# CP2102.net
KiCad netlist of a schematic drawn in Altium Designer
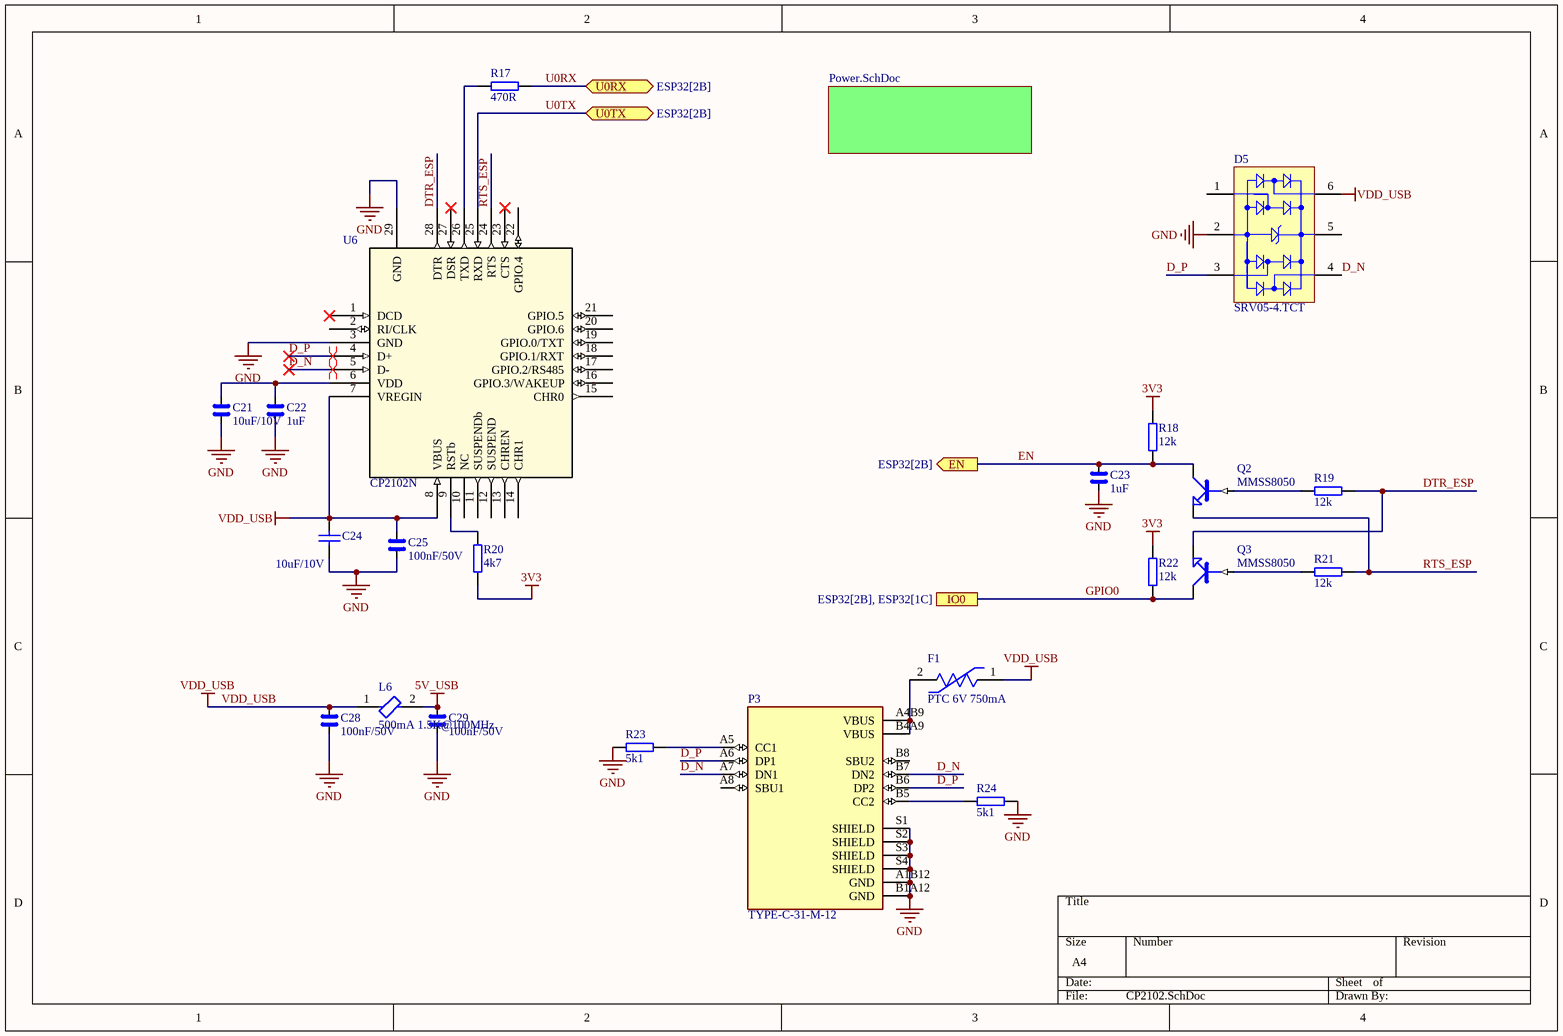
[diagram p0: CP2102.SchDoc]

(export (version "E")
  (design (tool "Eeschema 10.0.6"))
  (components
    (comp (ref "C21")
      (value "10uF/10V")
      (footprint "1608[0603]")
      (description "Capacitor")
      (fields (field (name "LCSCPARTNO") "C19702"))
      (libsource (lib "Sch") (part "C"))
    )
    (comp (ref "C22")
      (value "1uF")
      (footprint "1608[0603]")
      (description "CAP CER 1UF 10V X5R 0603")
      (fields (field (name "LCSCPARTNO") "C15849"))
      (libsource (lib "Sch") (part "C"))
    )
    (comp (ref "C23")
      (value "1uF")
      (footprint "1608[0603]")
      (description "CAP CER 1UF 10V X5R 0603")
      (fields (field (name "LCSCPARTNO") "C15849"))
      (libsource (lib "Sch") (part "C"))
    )
    (comp (ref "C24")
      (value "10uF/10V")
      (footprint "1608[0603]")
      (description "Capacitor")
      (fields (field (name "LCSCPARTNO") "C19702"))
      (libsource (lib "Sch") (part "Cap"))
    )
    (comp (ref "C25")
      (value "100nF/50V")
      (footprint "1608[0603]")
      (description "Cap Ceramic 0.1uF 50V X7R 20% SMD 0603 125C Paper T/R")
      (fields (field (name "LCSCPARTNO") "C14663"))
      (libsource (lib "Sch") (part "C"))
    )
    (comp (ref "C28")
      (value "100nF/50V")
      (footprint "1608[0603]")
      (description "Cap Ceramic 0.1uF 50V X7R 20% SMD 0603 125C Paper T/R")
      (fields (field (name "LCSCPARTNO") "C14663"))
      (libsource (lib "Sch") (part "C"))
    )
    (comp (ref "C29")
      (value "100nF/50V")
      (footprint "1608[0603]")
      (description "Cap Ceramic 0.1uF 50V X7R 20% SMD 0603 125C Paper T/R")
      (fields (field (name "LCSCPARTNO") "C14663"))
      (libsource (lib "Sch") (part "C"))
    )
    (comp (ref "D5")
      (value "SRV05-4.TCT")
      (footprint "SMTC-SOT23-6_V")
      (fields (field (name "LCSCPARTNO") "C85364"))
      (libsource (lib "Altium Content Vault") (part "STM-USB_DVI_HDMIULC6-4SC6X-SOT23-6L"))
    )
    (comp (ref "F1")
      (value "PTC 6V 750mA")
      (footprint "FP-1206L050YR-MFG")
      (description "PTC RESET FUSE 6V 750MA 1206")
      (fields (field (name "LCSCPARTNO") "C70078"))
      (libsource (lib "Altium Content Vault") (part "fdf083d5f6389a9a1c4e51137f46658"))
    )
    (comp (ref "L6")
      (value "500mA 1.5K@100MHz")
      (footprint "1608[0603]")
      (description "Chip Ferrite Bead, 0603, 1500Ω @ 100MHz, 0.5Ω, 25%, 500mA")
      (fields (field (name "LCSCPARTNO") "C82155"))
      (libsource (lib "Altium Content Vault") (part "5f30dd21d616792df468990f7003faa"))
    )
    (comp (ref "P3")
      (value "TYPE-C-31-M-12")
      (footprint "HRO_TYPE-C-31-M-12-3D")
      (description "USB Connectors 24 Receptacle 1 8.94*7.3mm RoHS")
      (fields (field (name "LCSCPARTNO") "C165948"))
      (libsource (lib "TYPE-C-31-M-12") (part "TYPE-C-31-M-12"))
    )
    (comp (ref "Q2")
      (value "MMSS8050")
      (footprint "SOT-23")
      (description "TRANS NPN 25V 1.5A SOT23")
      (fields (field (name "LCSCPARTNO") "C20526"))
      (libsource (lib "Sch") (part "NPN1"))
    )
    (comp (ref "Q3")
      (value "MMSS8050")
      (footprint "SOT-23")
      (description "TRANS NPN 25V 1.5A SOT23")
      (fields (field (name "LCSCPARTNO") "C20526"))
      (libsource (lib "Sch") (part "NPN1"))
    )
    (comp (ref "R17")
      (value "470R")
      (footprint "1608[0603]")
      (fields (field (name "LCSCPARTNO") "C23179"))
      (libsource (lib "Sch") (part "R"))
    )
    (comp (ref "R18")
      (value "12k")
      (footprint "1608[0603]")
      (description "Res Thick Film 0603 12K Ohm 1% 1/10W 100ppm/C Molded SMD SMD Paper T/R")
      (fields (field (name "LCSCPARTNO") "C22790"))
      (libsource (lib "Sch") (part "R"))
    )
    (comp (ref "R19")
      (value "12k")
      (footprint "1608[0603]")
      (description "Res Thick Film 0603 12K Ohm 1% 1/10W 100ppm/C Molded SMD SMD Paper T/R")
      (fields (field (name "LCSCPARTNO") "C22790"))
      (libsource (lib "Sch") (part "R"))
    )
    (comp (ref "R20")
      (value "4k7")
      (footprint "1608[0603]")
      (description "RES SMD 4.7K OHM 1% 1/10W 0603")
      (fields (field (name "LCSCPARTNO") "C23162"))
      (libsource (lib "Sch") (part "R"))
    )
    (comp (ref "R21")
      (value "12k")
      (footprint "1608[0603]")
      (description "Res Thick Film 0603 12K Ohm 1% 1/10W 100ppm/C Molded SMD SMD Paper T/R")
      (fields (field (name "LCSCPARTNO") "C22790"))
      (libsource (lib "Sch") (part "R"))
    )
    (comp (ref "R22")
      (value "12k")
      (footprint "1608[0603]")
      (description "Res Thick Film 0603 12K Ohm 1% 1/10W 100ppm/C Molded SMD SMD Paper T/R")
      (fields (field (name "LCSCPARTNO") "C22790"))
      (libsource (lib "Sch") (part "R"))
    )
    (comp (ref "R23")
      (value "5k1")
      (footprint "1608[0603]")
      (description "Res Thick Film 0603 5.1KOhm 1% 1/10W 100ppm/C Molded SMD SMD Paper T/R")
      (fields (field (name "LCSCPARTNO") "C23186"))
      (libsource (lib "Sch") (part "R"))
    )
    (comp (ref "R24")
      (value "5k1")
      (footprint "1608[0603]")
      (description "Res Thick Film 0603 5.1KOhm 1% 1/10W 100ppm/C Molded SMD SMD Paper T/R")
      (fields (field (name "LCSCPARTNO") "C23186"))
      (libsource (lib "Sch") (part "R"))
    )
    (comp (ref "U6")
      (value "CP2102N")
      (footprint "QFN28_5X5_SIL")
      (description "Full Speed USB to UART Bridge USB 2.0 3.3V Tube Automotive 28-Pin QFN EP")
      (fields (field (name "LCSCPARTNO") "C6568"))
      (libsource (lib "Sch") (part "CP2102N-A02-GQFN28"))
    )
  )
  (nets
    (net (code "1") (name "/DTR_ESP") (class "Default")
      (node (ref "Q3") (pin "2") (pinfunction "E_2") (pintype "passive"))
      (node (ref "R19") (pin "2") (pintype "passive"))
      (node (ref "U6") (pin "28") (pinfunction "DTR_28") (pintype "output"))
    )
    (net (code "2") (name "/D_N") (class "Default")
      (node (ref "D5") (pin "4") (pinfunction "I/O_3_4") (pintype "passive"))
      (node (ref "P3") (pin "A7") (pinfunction "DN1_A7") (pintype "bidirectional"))
      (node (ref "P3") (pin "B7") (pinfunction "DN2_B7") (pintype "bidirectional"))
      (node (ref "U6") (pin "5") (pinfunction "D-_5") (pintype "input"))
    )
    (net (code "3") (name "/D_P") (class "Default")
      (node (ref "D5") (pin "3") (pinfunction "I/O_2_3") (pintype "passive"))
      (node (ref "P3") (pin "A6") (pinfunction "DP1_A6") (pintype "bidirectional"))
      (node (ref "P3") (pin "B6") (pinfunction "DP2_B6") (pintype "bidirectional"))
      (node (ref "U6") (pin "4") (pinfunction "D+_4") (pintype "input"))
    )
    (net (code "4") (name "/EN") (class "Default")
      (node (ref "C23") (pin "1") (pinfunction "1_1") (pintype "passive"))
      (node (ref "Q2") (pin "3") (pinfunction "C_3") (pintype "passive"))
      (node (ref "R18") (pin "1") (pintype "passive"))
    )
    (net (code "5") (name "/GPIO0") (class "Default")
      (node (ref "Q3") (pin "3") (pinfunction "C_3") (pintype "passive"))
      (node (ref "R22") (pin "1") (pintype "passive"))
    )
    (net (code "6") (name "/RTS_ESP") (class "Default")
      (node (ref "Q2") (pin "2") (pinfunction "E_2") (pintype "passive"))
      (node (ref "R21") (pin "2") (pintype "passive"))
      (node (ref "U6") (pin "24") (pinfunction "RTS_24") (pintype "output"))
    )
    (net (code "7") (name "/U0RX") (class "Default") (node (ref "R17") (pin "1") (pintype "passive")))
    (net (code "8") (name "/U0TX") (class "Default")
      (node (ref "U6") (pin "25") (pinfunction "RXD_25") (pintype "input"))
    )
    (net (code "9") (name "3V3") (class "Default")
      (node (ref "R18") (pin "2") (pintype "passive"))
      (node (ref "R20") (pin "1") (pintype "passive"))
      (node (ref "R22") (pin "2") (pintype "passive"))
    )
    (net (code "10") (name "5V_USB") (class "Default")
      (node (ref "C29") (pin "1") (pinfunction "1_1") (pintype "passive"))
      (node (ref "L6") (pin "2") (pinfunction "2_2") (pintype "passive"))
    )
    (net (code "11") (name "GND") (class "Default")
      (node (ref "C21") (pin "2") (pinfunction "2_2") (pintype "passive"))
      (node (ref "C22") (pin "2") (pinfunction "2_2") (pintype "passive"))
      (node (ref "C23") (pin "2") (pinfunction "2_2") (pintype "passive"))
      (node (ref "C24") (pin "1") (pinfunction "1_1") (pintype "passive"))
      (node (ref "C25") (pin "2") (pinfunction "2_2") (pintype "passive"))
      (node (ref "C28") (pin "2") (pinfunction "2_2") (pintype "passive"))
      (node (ref "C29") (pin "2") (pinfunction "2_2") (pintype "passive"))
      (node (ref "D5") (pin "2") (pinfunction "GND_2") (pintype "passive"))
      (node (ref "P3") (pin "A1B12") (pinfunction "GND_A1B12") (pintype "power_in"))
      (node (ref "P3") (pin "B1A12") (pinfunction "GND_B1A12") (pintype "power_in"))
      (node (ref "P3") (pin "S1") (pinfunction "SHIELD_S1") (pintype "passive"))
      (node (ref "P3") (pin "S2") (pinfunction "SHIELD_S2") (pintype "passive"))
      (node (ref "P3") (pin "S3") (pinfunction "SHIELD_S3") (pintype "passive"))
      (node (ref "P3") (pin "S4") (pinfunction "SHIELD_S4") (pintype "passive"))
      (node (ref "R23") (pin "2") (pintype "passive"))
      (node (ref "R24") (pin "1") (pintype "passive"))
      (node (ref "U6") (pin "29") (pinfunction "GND_29") (pintype "passive"))
      (node (ref "U6") (pin "3") (pinfunction "GND_3") (pintype "passive"))
    )
    (net (code "12") (name "Net-(F1-Pad2)") (class "Default")
      (node (ref "F1") (pin "2") (pinfunction "2_2") (pintype "passive"))
      (node (ref "P3") (pin "A4B9") (pinfunction "VBUS_A4B9") (pintype "power_in"))
      (node (ref "P3") (pin "B4A9") (pinfunction "VBUS_B4A9") (pintype "power_in"))
    )
    (net (code "13") (name "Net-(P3-CC1)") (class "Default")
      (node (ref "P3") (pin "A5") (pinfunction "CC1_A5") (pintype "bidirectional"))
      (node (ref "R23") (pin "1") (pintype "passive"))
    )
    (net (code "14") (name "Net-(P3-CC2)") (class "Default")
      (node (ref "P3") (pin "B5") (pinfunction "CC2_B5") (pintype "bidirectional"))
      (node (ref "R24") (pin "2") (pintype "passive"))
    )
    (net (code "15") (name "Net-(Q2-B)") (class "Default")
      (node (ref "Q2") (pin "1") (pinfunction "B_1") (pintype "input"))
      (node (ref "R19") (pin "1") (pintype "passive"))
    )
    (net (code "16") (name "Net-(Q3-B)") (class "Default")
      (node (ref "Q3") (pin "1") (pinfunction "B_1") (pintype "input"))
      (node (ref "R21") (pin "1") (pintype "passive"))
    )
    (net (code "17") (name "Net-(U6-RSTb)") (class "Default")
      (node (ref "R20") (pin "2") (pintype "passive"))
      (node (ref "U6") (pin "9") (pinfunction "RSTb_9") (pintype "passive"))
    )
    (net (code "18") (name "Net-(U6-TXD)") (class "Default")
      (node (ref "R17") (pin "2") (pintype "passive"))
      (node (ref "U6") (pin "26") (pinfunction "TXD_26") (pintype "output"))
    )
    (net (code "19") (name "Net-(U6-VDD)") (class "Default")
      (node (ref "C21") (pin "1") (pinfunction "1_1") (pintype "passive"))
      (node (ref "C22") (pin "1") (pinfunction "1_1") (pintype "passive"))
      (node (ref "U6") (pin "6") (pinfunction "VDD_6") (pintype "power_in"))
    )
    (net (code "20") (name "VDD_USB") (class "Default")
      (node (ref "C24") (pin "2") (pinfunction "2_2") (pintype "passive"))
      (node (ref "C25") (pin "1") (pinfunction "1_1") (pintype "passive"))
      (node (ref "C28") (pin "1") (pinfunction "1_1") (pintype "passive"))
      (node (ref "D5") (pin "6") (pinfunction "I/O_4_6") (pintype "passive"))
      (node (ref "F1") (pin "1") (pinfunction "1_1") (pintype "passive"))
      (node (ref "L6") (pin "1") (pinfunction "1_1") (pintype "passive"))
      (node (ref "U6") (pin "7") (pinfunction "VREGIN_7") (pintype "power_in"))
      (node (ref "U6") (pin "8") (pinfunction "VBUS_8") (pintype "input"))
    )
    (net (code "21") (name "unconnected-(D5-I{slash}O_1-Pad1)") (class "Default")
      (node (ref "D5") (pin "1") (pinfunction "I/O_1_1") (pintype "passive"))
    )
    (net (code "22") (name "unconnected-(D5-VBUS-Pad5)") (class "Default")
      (node (ref "D5") (pin "5") (pinfunction "VBUS_5") (pintype "passive"))
    )
    (net (code "23") (name "unconnected-(P3-SBU1-PadA8)") (class "Default")
      (node (ref "P3") (pin "A8") (pinfunction "SBU1_A8") (pintype "bidirectional"))
    )
    (net (code "24") (name "unconnected-(P3-SBU2-PadB8)") (class "Default")
      (node (ref "P3") (pin "B8") (pinfunction "SBU2_B8") (pintype "bidirectional"))
    )
    (net (code "25") (name "unconnected-(U6-CHR0-Pad15)") (class "Default")
      (node (ref "U6") (pin "15") (pinfunction "CHR0_15") (pintype "output"))
    )
    (net (code "26") (name "unconnected-(U6-CHR1-Pad14)") (class "Default")
      (node (ref "U6") (pin "14") (pinfunction "CHR1_14") (pintype "output"))
    )
    (net (code "27") (name "unconnected-(U6-CHREN-Pad13)") (class "Default")
      (node (ref "U6") (pin "13") (pinfunction "CHREN_13") (pintype "output"))
    )
    (net (code "28") (name "unconnected-(U6-CTS-Pad23)") (class "Default")
      (node (ref "U6") (pin "23") (pinfunction "CTS_23") (pintype "input+no_connect"))
    )
    (net (code "29") (name "unconnected-(U6-DCD-Pad1)") (class "Default")
      (node (ref "U6") (pin "1") (pinfunction "DCD_1") (pintype "input+no_connect"))
    )
    (net (code "30") (name "unconnected-(U6-DSR-Pad27)") (class "Default")
      (node (ref "U6") (pin "27") (pinfunction "DSR_27") (pintype "input+no_connect"))
    )
    (net (code "31") (name "unconnected-(U6-GPIO.0{slash}TXT-Pad19)") (class "Default")
      (node (ref "U6") (pin "19") (pinfunction "GPIO.0/TXT_19") (pintype "bidirectional"))
    )
    (net (code "32") (name "unconnected-(U6-GPIO.1{slash}RXT-Pad18)") (class "Default")
      (node (ref "U6") (pin "18") (pinfunction "GPIO.1/RXT_18") (pintype "bidirectional"))
    )
    (net (code "33") (name "unconnected-(U6-GPIO.2{slash}RS485-Pad17)") (class "Default")
      (node (ref "U6") (pin "17") (pinfunction "GPIO.2/RS485_17") (pintype "bidirectional"))
    )
    (net (code "34") (name "unconnected-(U6-GPIO.3{slash}WAKEUP-Pad16)") (class "Default")
      (node (ref "U6") (pin "16") (pinfunction "GPIO.3/WAKEUP_16") (pintype "bidirectional"))
    )
    (net (code "35") (name "unconnected-(U6-GPIO.4-Pad22)") (class "Default")
      (node (ref "U6") (pin "22") (pinfunction "GPIO.4_22") (pintype "bidirectional"))
    )
    (net (code "36") (name "unconnected-(U6-GPIO.5-Pad21)") (class "Default")
      (node (ref "U6") (pin "21") (pinfunction "GPIO.5_21") (pintype "bidirectional"))
    )
    (net (code "37") (name "unconnected-(U6-GPIO.6-Pad20)") (class "Default")
      (node (ref "U6") (pin "20") (pinfunction "GPIO.6_20") (pintype "bidirectional"))
    )
    (net (code "38") (name "unconnected-(U6-NC-Pad10)") (class "Default")
      (node (ref "U6") (pin "10") (pinfunction "NC_10") (pintype "passive"))
    )
    (net (code "39") (name "unconnected-(U6-RI{slash}CLK-Pad2)") (class "Default")
      (node (ref "U6") (pin "2") (pinfunction "RI/CLK_2") (pintype "bidirectional"))
    )
    (net (code "40") (name "unconnected-(U6-SUSPEND-Pad12)") (class "Default")
      (node (ref "U6") (pin "12") (pinfunction "SUSPEND_12") (pintype "output"))
    )
    (net (code "41") (name "unconnected-(U6-SUSPENDb-Pad11)") (class "Default")
      (node (ref "U6") (pin "11") (pinfunction "SUSPENDb_11") (pintype "output"))
    )
  )
)
